# 99.net
KiCad netlist of a schematic drawn in EAGLE
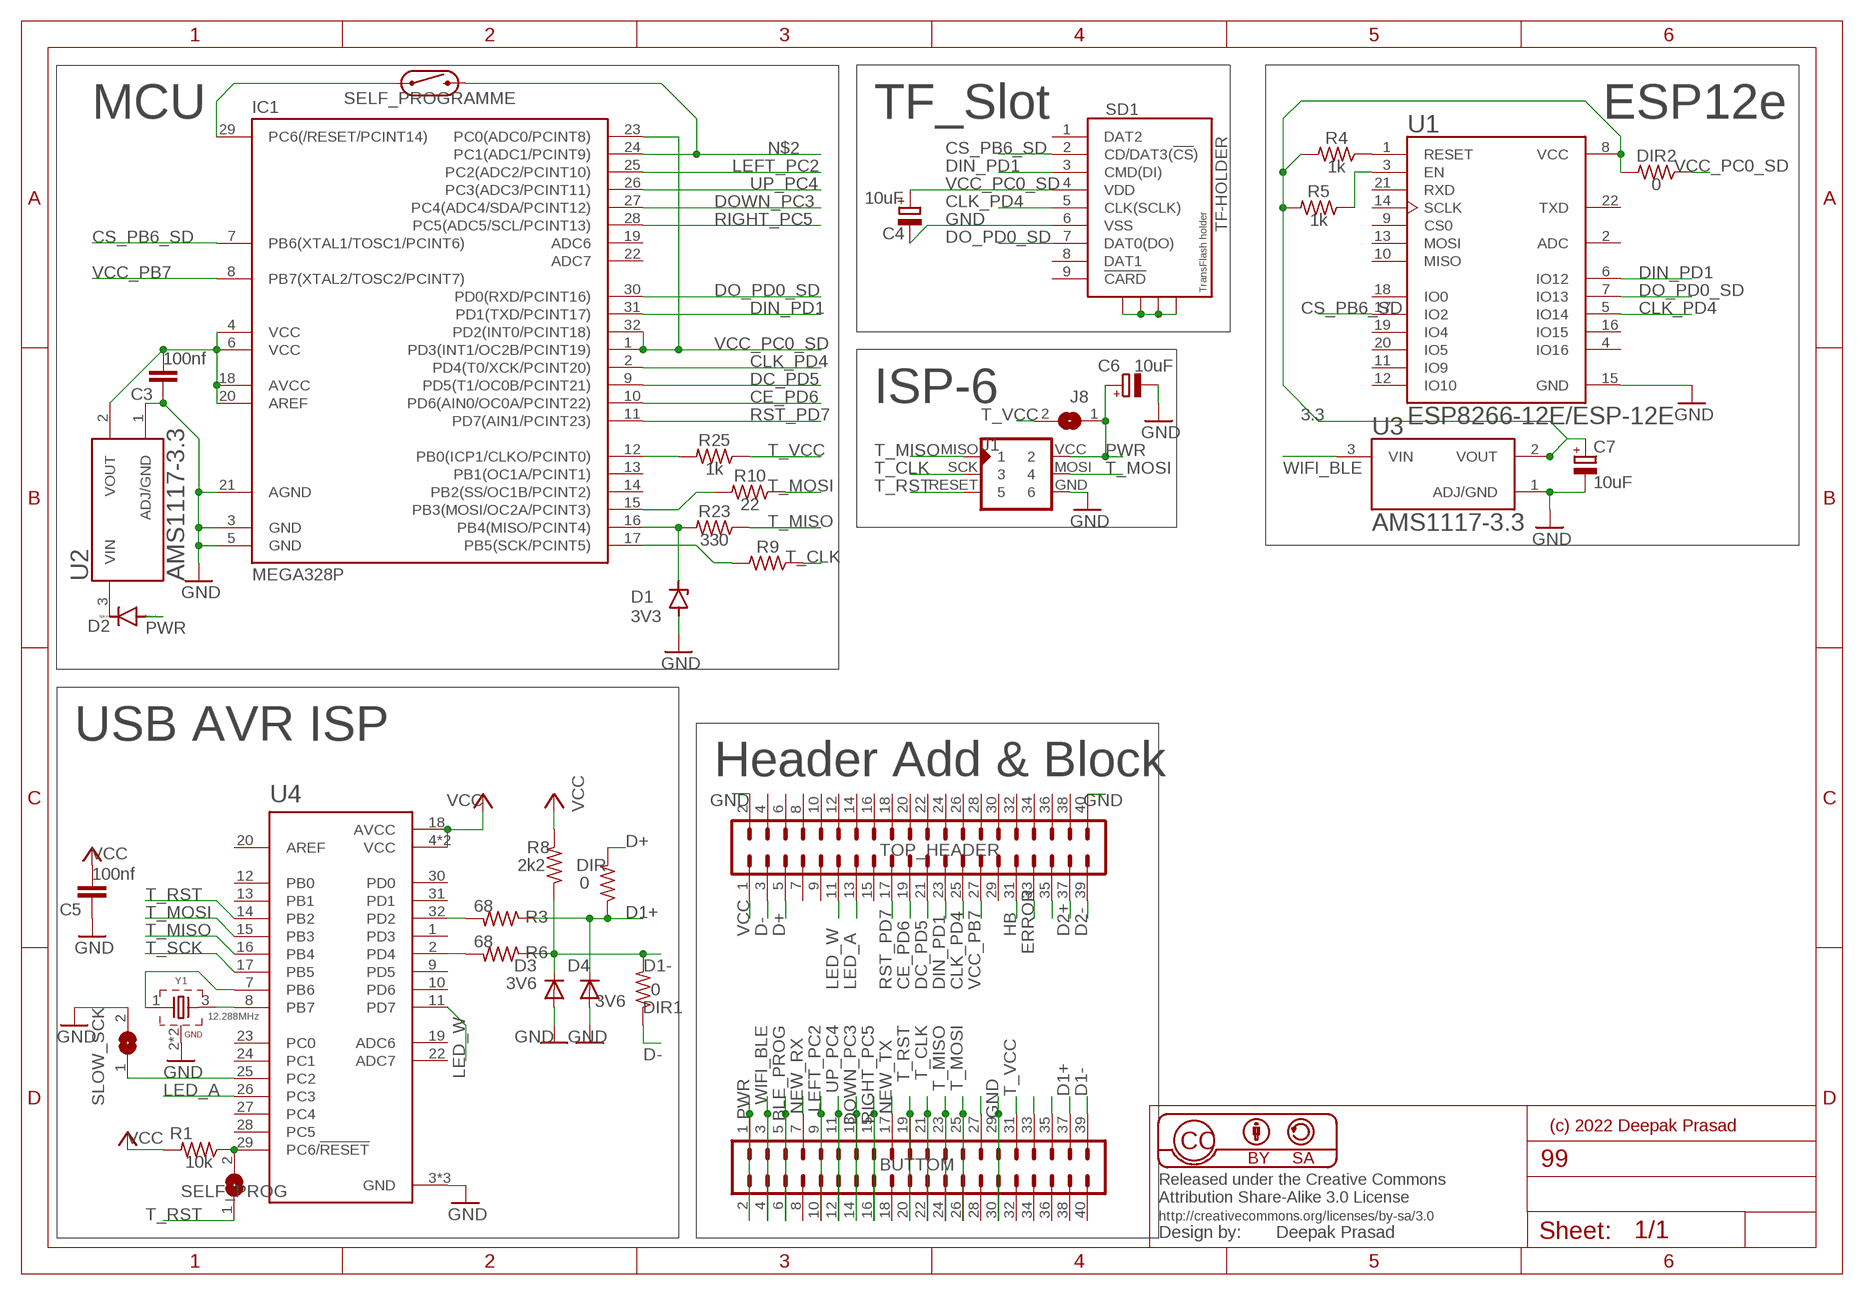
[diagram p0: schematic, sheet 1]

(export (version "E")
  (design (tool "Eeschema 10.0.6"))
  (components
    (comp (ref "BUTTOM")
      (value "MA20-2")
      (footprint "eagle-import:MA20-2")
      (libsource (lib "eagle-import") (part "MA20-2"))
    )
    (comp (ref "C3")
      (value "100nf")
      (footprint "eagle-import:C1206")
      (libsource (lib "eagle-import") (part "C-EUC1206"))
    )
    (comp (ref "C4")
      (value "10uF")
      (footprint "eagle-import:C_6032-28R")
      (libsource (lib "eagle-import") (part "CPOL-EUC/6032-28R"))
    )
    (comp (ref "C5")
      (value "100nf")
      (footprint "eagle-import:C1206")
      (libsource (lib "eagle-import") (part "C-EUC1206"))
    )
    (comp (ref "C6")
      (value "10uF")
      (footprint "eagle-import:C_6032-28R")
      (libsource (lib "eagle-import") (part "CPOL-EUC/6032-28R"))
    )
    (comp (ref "C7")
      (value "10uF")
      (footprint "eagle-import:C_6032-28R")
      (libsource (lib "eagle-import") (part "CPOL-EUC/6032-28R"))
    )
    (comp (ref "D1")
      (value "3V3")
      (footprint "eagle-import:SOD80C")
      (libsource (lib "eagle-import") (part "ZENER-DIODESOD80C"))
    )
    (comp (ref "D2")
      (value "DIODE-DO214AC")
      (footprint "eagle-import:DO214AC")
      (libsource (lib "eagle-import") (part "DIODE-DO214AC"))
    )
    (comp (ref "D3")
      (value "3V6")
      (footprint "eagle-import:SMA-DIODE")
      (libsource (lib "eagle-import") (part "DIODESMA"))
    )
    (comp (ref "D4")
      (value "3V6")
      (footprint "eagle-import:SMA-DIODE")
      (libsource (lib "eagle-import") (part "DIODESMA"))
    )
    (comp (ref "DIR")
      (value "0")
      (footprint "eagle-import:RESC3216X70")
      (libsource (lib "eagle-import") (part "R-USCHIP-1206(3216-METRIC)_"))
    )
    (comp (ref "DIR1")
      (value "0")
      (footprint "eagle-import:RESC3216X70")
      (libsource (lib "eagle-import") (part "R-USCHIP-1206(3216-METRIC)_"))
    )
    (comp (ref "DIR2")
      (value "0")
      (footprint "eagle-import:RESC3216X70")
      (libsource (lib "eagle-import") (part "R-USCHIP-1206(3216-METRIC)_"))
    )
    (comp (ref "IC1")
      (value "MEGA328P")
      (footprint "eagle-import:TQFP32-08")
      (libsource (lib "eagle-import") (part "MEGA48/88/168-AU"))
    )
    (comp (ref "J1")
      (value "AVR-ISP-6PINAVR-ISP-6PIN")
      (footprint "eagle-import:AVR-ISP-6PIN")
      (libsource (lib "eagle-import") (part "AVR-ISP-6PINAVR-ISP-6PIN"))
    )
    (comp (ref "J8")
      (value "SJW")
      (footprint "eagle-import:SJW")
      (libsource (lib "eagle-import") (part "SJW"))
    )
    (comp (ref "R1")
      (value "10k")
      (footprint "eagle-import:RESC3216X70")
      (libsource (lib "eagle-import") (part "R-USCHIP-1206(3216-METRIC)_"))
    )
    (comp (ref "R3")
      (value "68")
      (footprint "eagle-import:RESC3216X70")
      (libsource (lib "eagle-import") (part "R-USCHIP-1206(3216-METRIC)_"))
    )
    (comp (ref "R4")
      (value "1k")
      (footprint "eagle-import:RESC3216X70")
      (libsource (lib "eagle-import") (part "R-USCHIP-1206(3216-METRIC)_"))
    )
    (comp (ref "R5")
      (value "1k")
      (footprint "eagle-import:RESC3216X70")
      (libsource (lib "eagle-import") (part "R-USCHIP-1206(3216-METRIC)_"))
    )
    (comp (ref "R6")
      (value "68")
      (footprint "eagle-import:RESC3216X70")
      (libsource (lib "eagle-import") (part "R-USCHIP-1206(3216-METRIC)_"))
    )
    (comp (ref "R8")
      (value "2k2")
      (footprint "eagle-import:RESC3216X70")
      (libsource (lib "eagle-import") (part "R-USCHIP-1206(3216-METRIC)_"))
    )
    (comp (ref "R9")
      (value "22")
      (footprint "eagle-import:RESC3216X70")
      (libsource (lib "eagle-import") (part "R-USCHIP-1206(3216-METRIC)_"))
    )
    (comp (ref "R10")
      (value "22")
      (footprint "eagle-import:RESC3216X70")
      (libsource (lib "eagle-import") (part "R-USCHIP-1206(3216-METRIC)_"))
    )
    (comp (ref "R23")
      (value "330")
      (footprint "eagle-import:RESC3216X70")
      (libsource (lib "eagle-import") (part "R-USCHIP-1206(3216-METRIC)_"))
    )
    (comp (ref "R25")
      (value "1k")
      (footprint "eagle-import:RESC3216X70")
      (libsource (lib "eagle-import") (part "R-USCHIP-1206(3216-METRIC)_"))
    )
    (comp (ref "SD1")
      (value "TF-HOLDER")
      (footprint "eagle-import:TF-PULL")
      (libsource (lib "eagle-import") (part "TF-HOLDER"))
    )
    (comp (ref "SELF_PROG")
      (value "SJW")
      (footprint "eagle-import:SJW")
      (libsource (lib "eagle-import") (part "SJW"))
    )
    (comp (ref "SELF_PROGRAMME")
      (value "REED_SWITCH-PTH-GLASS")
      (footprint "eagle-import:REED_SWITCH_GLASS")
      (libsource (lib "eagle-import") (part "REED_SWITCH-PTH-GLASS"))
    )
    (comp (ref "SLOW_SCK")
      (value "SJW")
      (footprint "eagle-import:SJW")
      (libsource (lib "eagle-import") (part "SJW"))
    )
    (comp (ref "TOP_HEADER")
      (value "MA20-2")
      (footprint "eagle-import:MA20-2")
      (libsource (lib "eagle-import") (part "MA20-2"))
    )
    (comp (ref "U1")
      (value "ESP8266-12E/ESP-12E")
      (footprint "eagle-import:XCVR_ESP8266-12E_ESP-12E")
      (fields (field (name "MF") "AI-Thinker"))
      (libsource (lib "eagle-import") (part "ESP8266-12E/ESP-12E"))
    )
    (comp (ref "U2")
      (value "AMS1117-3.3")
      (footprint "eagle-import:SOT229P700X180-4N")
      (fields (field (name "MF") "Advanced Monolithic Systems"))
      (libsource (lib "eagle-import") (part "AMS1117-3.3"))
    )
    (comp (ref "U3")
      (value "AMS1117-3.3")
      (footprint "eagle-import:SOT229P700X180-4N")
      (fields (field (name "MF") "Advanced Monolithic Systems"))
      (libsource (lib "eagle-import") (part "AMS1117-3.3"))
    )
    (comp (ref "U4")
      (value "ATMEGA328P-AU")
      (footprint "eagle-import:QFP80P900X900X120-32N")
      (fields (field (name "MF") "Microchip Technology"))
      (libsource (lib "eagle-import") (part "ATMEGA328P-AU"))
    )
    (comp (ref "Y1")
      (value "12.288MHz")
      (footprint "eagle-import:WE-XTAL_CFPX-104")
      (fields (field (name "TOLERANCE") "±20ppm"))
      (libsource (lib "eagle-import") (part "WE-XTAL_CFPX-104_830059523"))
    )
  )
  (nets
    (net (code "1") (name "/3.3") (class "Default")
      (node (ref "C7") (pin "+") (pinfunction "+_+") (pintype "passive"))
      (node (ref "DIR2") (pin "2") (pinfunction "2_2") (pintype "passive"))
      (node (ref "R4") (pin "2") (pinfunction "2_2") (pintype "passive"))
      (node (ref "R5") (pin "2") (pinfunction "2_2") (pintype "passive"))
      (node (ref "U1") (pin "8") (pinfunction "VCC_8") (pintype "power_in"))
      (node (ref "U3") (pin "2") (pinfunction "VOUT_2") (pintype "output"))
    )
    (net (code "2") (name "/BLE_PROG") (class "Default")
      (node (ref "BUTTOM") (pin "5") (pinfunction "5_5") (pintype "passive"))
      (node (ref "BUTTOM") (pin "6") (pinfunction "6_6") (pintype "passive"))
    )
    (net (code "3") (name "/CE_PD6") (class "Default")
      (node (ref "IC1") (pin "10") (pinfunction "PD6(AIN0/OC0A/PCINT22)_10") (pintype "bidirectional"))
      (node (ref "TOP_HEADER") (pin "19") (pinfunction "19_19") (pintype "passive"))
    )
    (net (code "4") (name "/CLK_PD4") (class "Default")
      (node (ref "IC1") (pin "2") (pinfunction "PD4(T0/XCK/PCINT20)_2") (pintype "bidirectional"))
      (node (ref "SD1") (pin "5") (pinfunction "CLK(SCLK)_5") (pintype "input"))
      (node (ref "TOP_HEADER") (pin "25") (pinfunction "25_25") (pintype "passive"))
      (node (ref "U1") (pin "5") (pinfunction "IO14_5") (pintype "bidirectional"))
    )
    (net (code "5") (name "/CS_PB6_SD") (class "Default")
      (node (ref "IC1") (pin "7") (pinfunction "PB6(XTAL1/TOSC1/PCINT6)_7") (pintype "bidirectional"))
      (node (ref "SD1") (pin "2") (pinfunction "CD/DAT3(~{CS})_2") (pintype "bidirectional"))
      (node (ref "U1") (pin "17") (pinfunction "IO2_17") (pintype "bidirectional"))
    )
    (net (code "6") (name "/D+") (class "Default")
      (node (ref "DIR") (pin "2") (pinfunction "2_2") (pintype "passive"))
      (node (ref "TOP_HEADER") (pin "5") (pinfunction "5_5") (pintype "passive"))
    )
    (net (code "7") (name "/D-") (class "Default")
      (node (ref "DIR1") (pin "1") (pinfunction "1_1") (pintype "passive"))
      (node (ref "TOP_HEADER") (pin "3") (pinfunction "3_3") (pintype "passive"))
    )
    (net (code "8") (name "/D1+") (class "Default")
      (node (ref "BUTTOM") (pin "37") (pinfunction "37_37") (pintype "passive"))
      (node (ref "D4") (pin "C") (pinfunction "C_C") (pintype "passive"))
      (node (ref "DIR") (pin "1") (pinfunction "1_1") (pintype "passive"))
      (node (ref "R3") (pin "1") (pinfunction "1_1") (pintype "passive"))
    )
    (net (code "9") (name "/D1-") (class "Default")
      (node (ref "BUTTOM") (pin "39") (pinfunction "39_39") (pintype "passive"))
      (node (ref "D3") (pin "C") (pinfunction "C_C") (pintype "passive"))
      (node (ref "DIR1") (pin "2") (pinfunction "2_2") (pintype "passive"))
      (node (ref "R6") (pin "1") (pinfunction "1_1") (pintype "passive"))
      (node (ref "R8") (pin "1") (pinfunction "1_1") (pintype "passive"))
    )
    (net (code "10") (name "/D2+") (class "Default")
      (node (ref "TOP_HEADER") (pin "37") (pinfunction "37_37") (pintype "passive"))
    )
    (net (code "11") (name "/D2-") (class "Default")
      (node (ref "TOP_HEADER") (pin "39") (pinfunction "39_39") (pintype "passive"))
    )
    (net (code "12") (name "/DC_PD5") (class "Default")
      (node (ref "IC1") (pin "9") (pinfunction "PD5(T1/OC0B/PCINT21)_9") (pintype "bidirectional"))
      (node (ref "TOP_HEADER") (pin "21") (pinfunction "21_21") (pintype "passive"))
    )
    (net (code "13") (name "/DIN_PD1") (class "Default")
      (node (ref "IC1") (pin "31") (pinfunction "PD1(TXD/PCINT17)_31") (pintype "bidirectional"))
      (node (ref "SD1") (pin "3") (pinfunction "CMD(DI)_3") (pintype "bidirectional"))
      (node (ref "TOP_HEADER") (pin "23") (pinfunction "23_23") (pintype "passive"))
      (node (ref "U1") (pin "6") (pinfunction "IO12_6") (pintype "bidirectional"))
    )
    (net (code "14") (name "/DOWN_PC3") (class "Default")
      (node (ref "BUTTOM") (pin "13") (pinfunction "13_13") (pintype "passive"))
      (node (ref "BUTTOM") (pin "14") (pinfunction "14_14") (pintype "passive"))
      (node (ref "IC1") (pin "27") (pinfunction "PC4(ADC4/SDA/PCINT12)_27") (pintype "bidirectional"))
    )
    (net (code "15") (name "/DO_PD0_SD") (class "Default")
      (node (ref "IC1") (pin "30") (pinfunction "PD0(RXD/PCINT16)_30") (pintype "bidirectional"))
      (node (ref "SD1") (pin "7") (pinfunction "DAT0(DO)_7") (pintype "bidirectional"))
      (node (ref "U1") (pin "7") (pinfunction "IO13_7") (pintype "bidirectional"))
    )
    (net (code "16") (name "/ERROR") (class "Default")
      (node (ref "TOP_HEADER") (pin "33") (pinfunction "33_33") (pintype "passive"))
    )
    (net (code "17") (name "/HB") (class "Default")
      (node (ref "TOP_HEADER") (pin "31") (pinfunction "31_31") (pintype "passive"))
    )
    (net (code "18") (name "/LED_A") (class "Default")
      (node (ref "TOP_HEADER") (pin "13") (pinfunction "13_13") (pintype "passive"))
      (node (ref "U4") (pin "26") (pinfunction "PC3_26") (pintype "bidirectional"))
    )
    (net (code "19") (name "/LED_W") (class "Default")
      (node (ref "TOP_HEADER") (pin "11") (pinfunction "11_11") (pintype "passive"))
      (node (ref "U4") (pin "11") (pinfunction "PD7_11") (pintype "bidirectional"))
    )
    (net (code "20") (name "/LEFT_PC2") (class "Default")
      (node (ref "BUTTOM") (pin "10") (pinfunction "10_10") (pintype "passive"))
      (node (ref "BUTTOM") (pin "9") (pinfunction "9_9") (pintype "passive"))
      (node (ref "IC1") (pin "25") (pinfunction "PC2(ADC2/PCINT10)_25") (pintype "bidirectional"))
    )
    (net (code "21") (name "/N$2") (class "Default")
      (node (ref "IC1") (pin "24") (pinfunction "PC1(ADC1/PCINT9)_24") (pintype "bidirectional"))
      (node (ref "SELF_PROGRAMME") (pin "P$2") (pinfunction "2_P$2") (pintype "passive"))
    )
    (net (code "22") (name "/NEW_RX") (class "Default")
      (node (ref "BUTTOM") (pin "7") (pinfunction "7_7") (pintype "passive"))
    )
    (net (code "23") (name "/NEW_TX") (class "Default")
      (node (ref "BUTTOM") (pin "17") (pinfunction "17_17") (pintype "passive"))
    )
    (net (code "24") (name "/PWR") (class "Default")
      (node (ref "BUTTOM") (pin "1") (pinfunction "1_1") (pintype "passive"))
      (node (ref "BUTTOM") (pin "2") (pinfunction "2_2") (pintype "passive"))
      (node (ref "C6") (pin "+") (pinfunction "+_+") (pintype "passive"))
      (node (ref "D2") (pin "A") (pinfunction "A_A") (pintype "passive"))
      (node (ref "J1") (pin "VCC") (pinfunction "2_VCC") (pintype "passive"))
      (node (ref "J8") (pin "1") (pinfunction "1_1") (pintype "passive"))
    )
    (net (code "25") (name "/RIGHT_PC5") (class "Default")
      (node (ref "BUTTOM") (pin "15") (pinfunction "15_15") (pintype "passive"))
      (node (ref "BUTTOM") (pin "16") (pinfunction "16_16") (pintype "passive"))
      (node (ref "IC1") (pin "28") (pinfunction "PC5(ADC5/SCL/PCINT13)_28") (pintype "bidirectional"))
    )
    (net (code "26") (name "/RST_PD7") (class "Default")
      (node (ref "IC1") (pin "11") (pinfunction "PD7(AIN1/PCINT23)_11") (pintype "bidirectional"))
      (node (ref "TOP_HEADER") (pin "17") (pinfunction "17_17") (pintype "passive"))
    )
    (net (code "27") (name "/T_CLK") (class "Default")
      (node (ref "BUTTOM") (pin "21") (pinfunction "21_21") (pintype "passive"))
      (node (ref "BUTTOM") (pin "22") (pinfunction "22_22") (pintype "passive"))
      (node (ref "J1") (pin "SCK") (pinfunction "3_SCK") (pintype "passive"))
      (node (ref "R9") (pin "1") (pinfunction "1_1") (pintype "passive"))
    )
    (net (code "28") (name "/T_MISO") (class "Default")
      (node (ref "BUTTOM") (pin "23") (pinfunction "23_23") (pintype "passive"))
      (node (ref "BUTTOM") (pin "24") (pinfunction "24_24") (pintype "passive"))
      (node (ref "J1") (pin "MISO") (pinfunction "1_MISO") (pintype "passive"))
      (node (ref "R23") (pin "1") (pinfunction "1_1") (pintype "passive"))
      (node (ref "U4") (pin "16") (pinfunction "PB4_16") (pintype "bidirectional"))
    )
    (net (code "29") (name "/T_MOSI") (class "Default")
      (node (ref "BUTTOM") (pin "25") (pinfunction "25_25") (pintype "passive"))
      (node (ref "BUTTOM") (pin "26") (pinfunction "26_26") (pintype "passive"))
      (node (ref "J1") (pin "MOSI") (pinfunction "4_MOSI") (pintype "passive"))
      (node (ref "R10") (pin "1") (pinfunction "1_1") (pintype "passive"))
      (node (ref "U4") (pin "15") (pinfunction "PB3_15") (pintype "bidirectional"))
    )
    (net (code "30") (name "/T_RST") (class "Default")
      (node (ref "BUTTOM") (pin "19") (pinfunction "19_19") (pintype "passive"))
      (node (ref "BUTTOM") (pin "20") (pinfunction "20_20") (pintype "passive"))
      (node (ref "J1") (pin "RESET") (pinfunction "5_RESET") (pintype "passive"))
      (node (ref "SELF_PROG") (pin "1") (pinfunction "1_1") (pintype "passive"))
      (node (ref "U4") (pin "14") (pinfunction "PB2_14") (pintype "bidirectional"))
    )
    (net (code "31") (name "/T_SCK") (class "Default")
      (node (ref "U4") (pin "17") (pinfunction "PB5_17") (pintype "bidirectional"))
    )
    (net (code "32") (name "/T_VCC") (class "Default")
      (node (ref "BUTTOM") (pin "31") (pinfunction "31_31") (pintype "passive"))
      (node (ref "J8") (pin "2") (pinfunction "2_2") (pintype "passive"))
      (node (ref "R25") (pin "1") (pinfunction "1_1") (pintype "passive"))
    )
    (net (code "33") (name "/UP_PC4") (class "Default")
      (node (ref "BUTTOM") (pin "11") (pinfunction "11_11") (pintype "passive"))
      (node (ref "BUTTOM") (pin "12") (pinfunction "12_12") (pintype "passive"))
      (node (ref "IC1") (pin "26") (pinfunction "PC3(ADC3/PCINT11)_26") (pintype "bidirectional"))
    )
    (net (code "34") (name "/VCC_PB7") (class "Default")
      (node (ref "IC1") (pin "8") (pinfunction "PB7(XTAL2/TOSC2/PCINT7)_8") (pintype "bidirectional"))
      (node (ref "TOP_HEADER") (pin "27") (pinfunction "27_27") (pintype "passive"))
    )
    (net (code "35") (name "/VCC_PC0_SD") (class "Default")
      (node (ref "C4") (pin "+") (pinfunction "+_+") (pintype "passive"))
      (node (ref "DIR2") (pin "1") (pinfunction "1_1") (pintype "passive"))
      (node (ref "IC1") (pin "1") (pinfunction "PD3(INT1/OC2B/PCINT19)_1") (pintype "bidirectional"))
      (node (ref "IC1") (pin "23") (pinfunction "PC0(ADC0/PCINT8)_23") (pintype "bidirectional"))
      (node (ref "IC1") (pin "32") (pinfunction "PD2(INT0/PCINT18)_32") (pintype "bidirectional"))
      (node (ref "SD1") (pin "4") (pinfunction "VDD_4") (pintype "power_in"))
    )
    (net (code "36") (name "/WIFI_BLE") (class "Default")
      (node (ref "BUTTOM") (pin "3") (pinfunction "3_3") (pintype "passive"))
      (node (ref "BUTTOM") (pin "4") (pinfunction "4_4") (pintype "passive"))
      (node (ref "U3") (pin "3") (pinfunction "VIN_3") (pintype "input"))
    )
    (net (code "37") (name "GND") (class "Default")
      (node (ref "BUTTOM") (pin "29") (pinfunction "29_29") (pintype "passive"))
      (node (ref "BUTTOM") (pin "30") (pinfunction "30_30") (pintype "passive"))
      (node (ref "C3") (pin "1") (pinfunction "1_1") (pintype "passive"))
      (node (ref "C4") (pin "-") (pinfunction "-_-") (pintype "passive"))
      (node (ref "C5") (pin "1") (pinfunction "1_1") (pintype "passive"))
      (node (ref "C6") (pin "-") (pinfunction "-_-") (pintype "passive"))
      (node (ref "C7") (pin "-") (pinfunction "-_-") (pintype "passive"))
      (node (ref "D1") (pin "A") (pinfunction "A_A") (pintype "passive"))
      (node (ref "D3") (pin "A") (pinfunction "A_A") (pintype "passive"))
      (node (ref "D4") (pin "A") (pinfunction "A_A") (pintype "passive"))
      (node (ref "IC1") (pin "21") (pinfunction "AGND_21") (pintype "power_in"))
      (node (ref "IC1") (pin "3") (pinfunction "GND_3") (pintype "power_in"))
      (node (ref "IC1") (pin "5") (pinfunction "GND_5") (pintype "power_in"))
      (node (ref "J1") (pin "GND") (pinfunction "6_GND") (pintype "passive"))
      (node (ref "SD1") (pin "6") (pinfunction "VSS_6") (pintype "power_in"))
      (node (ref "SLOW_SCK") (pin "2") (pinfunction "2_2") (pintype "passive"))
      (node (ref "TOP_HEADER") (pin "2") (pinfunction "2_2") (pintype "passive"))
      (node (ref "TOP_HEADER") (pin "40") (pinfunction "40_40") (pintype "passive"))
      (node (ref "U1") (pin "15") (pinfunction "GND_15") (pintype "power_in"))
      (node (ref "U2") (pin "1") (pinfunction "ADJ/GND_1") (pintype "power_in"))
      (node (ref "U3") (pin "1") (pinfunction "ADJ/GND_1") (pintype "power_in"))
      (node (ref "U4") (pin "21") (pinfunction "GND_21") (pintype "power_in"))
      (node (ref "U4") (pin "3") (pinfunction "GND_3") (pintype "power_in"))
      (node (ref "U4") (pin "5") (pinfunction "GND_5") (pintype "power_in"))
      (node (ref "Y1") (pin "2") (pinfunction "GND_2") (pintype "passive"))
      (node (ref "Y1") (pin "4") (pinfunction "GND_4") (pintype "passive"))
    )
    (net (code "38") (name "Net-(IC1-AREF)") (class "Default")
      (node (ref "C3") (pin "2") (pinfunction "2_2") (pintype "passive"))
      (node (ref "IC1") (pin "18") (pinfunction "AVCC_18") (pintype "passive"))
      (node (ref "IC1") (pin "20") (pinfunction "AREF_20") (pintype "passive"))
      (node (ref "IC1") (pin "4") (pinfunction "VCC_4") (pintype "power_in"))
      (node (ref "IC1") (pin "6") (pinfunction "VCC_6") (pintype "power_in"))
      (node (ref "U2") (pin "2") (pinfunction "VOUT_2") (pintype "output"))
    )
    (net (code "39") (name "Net-(IC1-PB0(ICP1{slash}CLKO{slash}PCINT0))") (class "Default")
      (node (ref "IC1") (pin "12") (pinfunction "PB0(ICP1/CLKO/PCINT0)_12") (pintype "bidirectional"))
      (node (ref "R25") (pin "2") (pinfunction "2_2") (pintype "passive"))
    )
    (net (code "40") (name "Net-(IC1-PB3(MOSI{slash}OC2A{slash}PCINT3))") (class "Default")
      (node (ref "IC1") (pin "15") (pinfunction "PB3(MOSI/OC2A/PCINT3)_15") (pintype "bidirectional"))
      (node (ref "R10") (pin "2") (pinfunction "2_2") (pintype "passive"))
    )
    (net (code "41") (name "Net-(IC1-PB4(MISO{slash}PCINT4))") (class "Default")
      (node (ref "D1") (pin "C") (pinfunction "C_C") (pintype "passive"))
      (node (ref "IC1") (pin "16") (pinfunction "PB4(MISO/PCINT4)_16") (pintype "bidirectional"))
      (node (ref "R23") (pin "2") (pinfunction "2_2") (pintype "passive"))
    )
    (net (code "42") (name "Net-(IC1-PB5(SCK{slash}PCINT5))") (class "Default")
      (node (ref "IC1") (pin "17") (pinfunction "PB5(SCK/PCINT5)_17") (pintype "bidirectional"))
      (node (ref "R9") (pin "2") (pinfunction "2_2") (pintype "passive"))
    )
    (net (code "43") (name "Net-(IC1-PC6({slash}RESET{slash}PCINT14))") (class "Default")
      (node (ref "IC1") (pin "29") (pinfunction "PC6(/RESET/PCINT14)_29") (pintype "bidirectional"))
      (node (ref "SELF_PROGRAMME") (pin "P$1") (pinfunction "1_P$1") (pintype "passive"))
    )
    (net (code "44") (name "Net-(SD1-PadS1)") (class "Default")
      (node (ref "SD1") (pin "S1") (pinfunction "S1_S1") (pintype "passive"))
      (node (ref "SD1") (pin "S2") (pinfunction "S2_S2") (pintype "passive"))
      (node (ref "SD1") (pin "S3") (pinfunction "S3_S3") (pintype "passive"))
      (node (ref "SD1") (pin "S4") (pinfunction "S4_S4") (pintype "passive"))
    )
    (net (code "45") (name "Net-(U1-EN)") (class "Default")
      (node (ref "R5") (pin "1") (pinfunction "1_1") (pintype "passive"))
      (node (ref "U1") (pin "3") (pinfunction "EN_3") (pintype "input"))
    )
    (net (code "46") (name "Net-(U1-RESET)") (class "Default")
      (node (ref "R4") (pin "1") (pinfunction "1_1") (pintype "passive"))
      (node (ref "U1") (pin "1") (pinfunction "RESET_1") (pintype "input"))
    )
    (net (code "47") (name "Net-(U2-VIN)") (class "Default")
      (node (ref "D2") (pin "C") (pinfunction "C_C") (pintype "passive"))
      (node (ref "U2") (pin "3") (pinfunction "VIN_3") (pintype "input"))
    )
    (net (code "48") (name "Net-(U4-PB6)") (class "Default")
      (node (ref "U4") (pin "7") (pinfunction "PB6_7") (pintype "bidirectional"))
      (node (ref "Y1") (pin "1") (pinfunction "1_1") (pintype "passive"))
    )
    (net (code "49") (name "Net-(U4-PB7)") (class "Default")
      (node (ref "U4") (pin "8") (pinfunction "PB7_8") (pintype "bidirectional"))
      (node (ref "Y1") (pin "3") (pinfunction "2_3") (pintype "passive"))
    )
    (net (code "50") (name "Net-(U4-PC2)") (class "Default")
      (node (ref "SLOW_SCK") (pin "1") (pinfunction "1_1") (pintype "passive"))
      (node (ref "U4") (pin "25") (pinfunction "PC2_25") (pintype "bidirectional"))
    )
    (net (code "51") (name "Net-(U4-PC6{slash}~{RESET})") (class "Default")
      (node (ref "R1") (pin "1") (pinfunction "1_1") (pintype "passive"))
      (node (ref "SELF_PROG") (pin "2") (pinfunction "2_2") (pintype "passive"))
      (node (ref "U4") (pin "29") (pinfunction "PC6/~{RESET}_29") (pintype "bidirectional"))
    )
    (net (code "52") (name "Net-(U4-PD2)") (class "Default")
      (node (ref "R3") (pin "2") (pinfunction "2_2") (pintype "passive"))
      (node (ref "U4") (pin "32") (pinfunction "PD2_32") (pintype "bidirectional"))
    )
    (net (code "53") (name "Net-(U4-PD4)") (class "Default")
      (node (ref "R6") (pin "2") (pinfunction "2_2") (pintype "passive"))
      (node (ref "U4") (pin "2") (pinfunction "PD4_2") (pintype "bidirectional"))
    )
    (net (code "54") (name "VCC") (class "Default")
      (node (ref "C5") (pin "2") (pinfunction "2_2") (pintype "passive"))
      (node (ref "R1") (pin "2") (pinfunction "2_2") (pintype "passive"))
      (node (ref "R8") (pin "2") (pinfunction "2_2") (pintype "passive"))
      (node (ref "TOP_HEADER") (pin "1") (pinfunction "1_1") (pintype "passive"))
      (node (ref "U4") (pin "18") (pinfunction "AVCC_18") (pintype "power_in"))
      (node (ref "U4") (pin "4") (pinfunction "VCC_4") (pintype "power_in"))
      (node (ref "U4") (pin "6") (pinfunction "VCC_6") (pintype "power_in"))
    )
    (net (code "55") (name "unconnected-(BUTTOM-Pad8)") (class "Default")
      (node (ref "BUTTOM") (pin "8") (pinfunction "8_8") (pintype "passive"))
    )
    (net (code "56") (name "unconnected-(BUTTOM-Pad18)") (class "Default")
      (node (ref "BUTTOM") (pin "18") (pinfunction "18_18") (pintype "passive"))
    )
    (net (code "57") (name "unconnected-(BUTTOM-Pad27)") (class "Default")
      (node (ref "BUTTOM") (pin "27") (pinfunction "27_27") (pintype "passive"))
    )
    (net (code "58") (name "unconnected-(BUTTOM-Pad28)") (class "Default")
      (node (ref "BUTTOM") (pin "28") (pinfunction "28_28") (pintype "passive"))
    )
    (net (code "59") (name "unconnected-(BUTTOM-Pad32)") (class "Default")
      (node (ref "BUTTOM") (pin "32") (pinfunction "32_32") (pintype "passive"))
    )
    (net (code "60") (name "unconnected-(BUTTOM-Pad33)") (class "Default")
      (node (ref "BUTTOM") (pin "33") (pinfunction "33_33") (pintype "passive"))
    )
    (net (code "61") (name "unconnected-(BUTTOM-Pad34)") (class "Default")
      (node (ref "BUTTOM") (pin "34") (pinfunction "34_34") (pintype "passive"))
    )
    (net (code "62") (name "unconnected-(BUTTOM-Pad35)") (class "Default")
      (node (ref "BUTTOM") (pin "35") (pinfunction "35_35") (pintype "passive"))
    )
    (net (code "63") (name "unconnected-(BUTTOM-Pad36)") (class "Default")
      (node (ref "BUTTOM") (pin "36") (pinfunction "36_36") (pintype "passive"))
    )
    (net (code "64") (name "unconnected-(BUTTOM-Pad38)") (class "Default")
      (node (ref "BUTTOM") (pin "38") (pinfunction "38_38") (pintype "passive"))
    )
    (net (code "65") (name "unconnected-(BUTTOM-Pad40)") (class "Default")
      (node (ref "BUTTOM") (pin "40") (pinfunction "40_40") (pintype "passive"))
    )
    (net (code "66") (name "unconnected-(IC1-ADC6-Pad19)") (class "Default")
      (node (ref "IC1") (pin "19") (pinfunction "ADC6_19") (pintype "passive"))
    )
    (net (code "67") (name "unconnected-(IC1-ADC7-Pad22)") (class "Default")
      (node (ref "IC1") (pin "22") (pinfunction "ADC7_22") (pintype "passive"))
    )
    (net (code "68") (name "unconnected-(IC1-PB1(OC1A{slash}PCINT1)-Pad13)") (class "Default")
      (node (ref "IC1") (pin "13") (pinfunction "PB1(OC1A/PCINT1)_13") (pintype "bidirectional"))
    )
    (net (code "69") (name "unconnected-(IC1-PB2(SS{slash}OC1B{slash}PCINT2)-Pad14)") (class "Default")
      (node (ref "IC1") (pin "14") (pinfunction "PB2(SS/OC1B/PCINT2)_14") (pintype "bidirectional"))
    )
    (net (code "70") (name "unconnected-(SD1-DAT1-Pad8)") (class "Default")
      (node (ref "SD1") (pin "8") (pinfunction "DAT1_8") (pintype "bidirectional"))
    )
    (net (code "71") (name "unconnected-(SD1-DAT2-Pad1)") (class "Default")
      (node (ref "SD1") (pin "1") (pinfunction "DAT2_1") (pintype "bidirectional"))
    )
    (net (code "72") (name "unconnected-(SD1-~{CARD}-Pad9)") (class "Default")
      (node (ref "SD1") (pin "9") (pinfunction "~{CARD}_9") (pintype "passive"))
    )
    (net (code "73") (name "unconnected-(TOP_HEADER-Pad4)") (class "Default")
      (node (ref "TOP_HEADER") (pin "4") (pinfunction "4_4") (pintype "passive"))
    )
    (net (code "74") (name "unconnected-(TOP_HEADER-Pad6)") (class "Default")
      (node (ref "TOP_HEADER") (pin "6") (pinfunction "6_6") (pintype "passive"))
    )
    (net (code "75") (name "unconnected-(TOP_HEADER-Pad7)") (class "Default")
      (node (ref "TOP_HEADER") (pin "7") (pinfunction "7_7") (pintype "passive"))
    )
    (net (code "76") (name "unconnected-(TOP_HEADER-Pad8)") (class "Default")
      (node (ref "TOP_HEADER") (pin "8") (pinfunction "8_8") (pintype "passive"))
    )
    (net (code "77") (name "unconnected-(TOP_HEADER-Pad9)") (class "Default")
      (node (ref "TOP_HEADER") (pin "9") (pinfunction "9_9") (pintype "passive"))
    )
    (net (code "78") (name "unconnected-(TOP_HEADER-Pad10)") (class "Default")
      (node (ref "TOP_HEADER") (pin "10") (pinfunction "10_10") (pintype "passive"))
    )
    (net (code "79") (name "unconnected-(TOP_HEADER-Pad12)") (class "Default")
      (node (ref "TOP_HEADER") (pin "12") (pinfunction "12_12") (pintype "passive"))
    )
    (net (code "80") (name "unconnected-(TOP_HEADER-Pad14)") (class "Default")
      (node (ref "TOP_HEADER") (pin "14") (pinfunction "14_14") (pintype "passive"))
    )
    (net (code "81") (name "unconnected-(TOP_HEADER-Pad15)") (class "Default")
      (node (ref "TOP_HEADER") (pin "15") (pinfunction "15_15") (pintype "passive"))
    )
    (net (code "82") (name "unconnected-(TOP_HEADER-Pad16)") (class "Default")
      (node (ref "TOP_HEADER") (pin "16") (pinfunction "16_16") (pintype "passive"))
    )
    (net (code "83") (name "unconnected-(TOP_HEADER-Pad18)") (class "Default")
      (node (ref "TOP_HEADER") (pin "18") (pinfunction "18_18") (pintype "passive"))
    )
    (net (code "84") (name "unconnected-(TOP_HEADER-Pad20)") (class "Default")
      (node (ref "TOP_HEADER") (pin "20") (pinfunction "20_20") (pintype "passive"))
    )
    (net (code "85") (name "unconnected-(TOP_HEADER-Pad22)") (class "Default")
      (node (ref "TOP_HEADER") (pin "22") (pinfunction "22_22") (pintype "passive"))
    )
    (net (code "86") (name "unconnected-(TOP_HEADER-Pad24)") (class "Default")
      (node (ref "TOP_HEADER") (pin "24") (pinfunction "24_24") (pintype "passive"))
    )
    (net (code "87") (name "unconnected-(TOP_HEADER-Pad26)") (class "Default")
      (node (ref "TOP_HEADER") (pin "26") (pinfunction "26_26") (pintype "passive"))
    )
    (net (code "88") (name "unconnected-(TOP_HEADER-Pad28)") (class "Default")
      (node (ref "TOP_HEADER") (pin "28") (pinfunction "28_28") (pintype "passive"))
    )
    (net (code "89") (name "unconnected-(TOP_HEADER-Pad29)") (class "Default")
      (node (ref "TOP_HEADER") (pin "29") (pinfunction "29_29") (pintype "passive"))
    )
    (net (code "90") (name "unconnected-(TOP_HEADER-Pad30)") (class "Default")
      (node (ref "TOP_HEADER") (pin "30") (pinfunction "30_30") (pintype "passive"))
    )
    (net (code "91") (name "unconnected-(TOP_HEADER-Pad32)") (class "Default")
      (node (ref "TOP_HEADER") (pin "32") (pinfunction "32_32") (pintype "passive"))
    )
    (net (code "92") (name "unconnected-(TOP_HEADER-Pad34)") (class "Default")
      (node (ref "TOP_HEADER") (pin "34") (pinfunction "34_34") (pintype "passive"))
    )
    (net (code "93") (name "unconnected-(TOP_HEADER-Pad35)") (class "Default")
      (node (ref "TOP_HEADER") (pin "35") (pinfunction "35_35") (pintype "passive"))
    )
    (net (code "94") (name "unconnected-(TOP_HEADER-Pad36)") (class "Default")
      (node (ref "TOP_HEADER") (pin "36") (pinfunction "36_36") (pintype "passive"))
    )
    (net (code "95") (name "unconnected-(TOP_HEADER-Pad38)") (class "Default")
      (node (ref "TOP_HEADER") (pin "38") (pinfunction "38_38") (pintype "passive"))
    )
    (net (code "96") (name "unconnected-(U1-ADC-Pad2)") (class "Default")
      (node (ref "U1") (pin "2") (pinfunction "ADC_2") (pintype "passive"))
    )
    (net (code "97") (name "unconnected-(U1-CS0-Pad9)") (class "Default")
      (node (ref "U1") (pin "9") (pinfunction "CS0_9") (pintype "input"))
    )
    (net (code "98") (name "unconnected-(U1-IO0-Pad18)") (class "Default")
      (node (ref "U1") (pin "18") (pinfunction "IO0_18") (pintype "bidirectional"))
    )
    (net (code "99") (name "unconnected-(U1-IO4-Pad19)") (class "Default")
      (node (ref "U1") (pin "19") (pinfunction "IO4_19") (pintype "bidirectional"))
    )
    (net (code "100") (name "unconnected-(U1-IO5-Pad20)") (class "Default")
      (node (ref "U1") (pin "20") (pinfunction "IO5_20") (pintype "bidirectional"))
    )
    (net (code "101") (name "unconnected-(U1-IO9-Pad11)") (class "Default")
      (node (ref "U1") (pin "11") (pinfunction "IO9_11") (pintype "bidirectional"))
    )
    (net (code "102") (name "unconnected-(U1-IO10-Pad12)") (class "Default")
      (node (ref "U1") (pin "12") (pinfunction "IO10_12") (pintype "bidirectional"))
    )
    (net (code "103") (name "unconnected-(U1-IO15-Pad16)") (class "Default")
      (node (ref "U1") (pin "16") (pinfunction "IO15_16") (pintype "bidirectional"))
    )
    (net (code "104") (name "unconnected-(U1-IO16-Pad4)") (class "Default")
      (node (ref "U1") (pin "4") (pinfunction "IO16_4") (pintype "bidirectional"))
    )
    (net (code "105") (name "unconnected-(U1-MISO-Pad10)") (class "Default")
      (node (ref "U1") (pin "10") (pinfunction "MISO_10") (pintype "bidirectional"))
    )
    (net (code "106") (name "unconnected-(U1-MOSI-Pad13)") (class "Default")
      (node (ref "U1") (pin "13") (pinfunction "MOSI_13") (pintype "bidirectional"))
    )
    (net (code "107") (name "unconnected-(U1-RXD-Pad21)") (class "Default")
      (node (ref "U1") (pin "21") (pinfunction "RXD_21") (pintype "input"))
    )
    (net (code "108") (name "unconnected-(U1-SCLK-Pad14)") (class "Default")
      (node (ref "U1") (pin "14") (pinfunction "SCLK_14") (pintype "input"))
    )
    (net (code "109") (name "unconnected-(U1-TXD-Pad22)") (class "Default")
      (node (ref "U1") (pin "22") (pinfunction "TXD_22") (pintype "output"))
    )
    (net (code "110") (name "unconnected-(U4-ADC6-Pad19)") (class "Default")
      (node (ref "U4") (pin "19") (pinfunction "ADC6_19") (pintype "bidirectional"))
    )
    (net (code "111") (name "unconnected-(U4-ADC7-Pad22)") (class "Default")
      (node (ref "U4") (pin "22") (pinfunction "ADC7_22") (pintype "bidirectional"))
    )
    (net (code "112") (name "unconnected-(U4-AREF-Pad20)") (class "Default")
      (node (ref "U4") (pin "20") (pinfunction "AREF_20") (pintype "input"))
    )
    (net (code "113") (name "unconnected-(U4-PB0-Pad12)") (class "Default")
      (node (ref "U4") (pin "12") (pinfunction "PB0_12") (pintype "bidirectional"))
    )
    (net (code "114") (name "unconnected-(U4-PB1-Pad13)") (class "Default")
      (node (ref "U4") (pin "13") (pinfunction "PB1_13") (pintype "bidirectional"))
    )
    (net (code "115") (name "unconnected-(U4-PC0-Pad23)") (class "Default")
      (node (ref "U4") (pin "23") (pinfunction "PC0_23") (pintype "bidirectional"))
    )
    (net (code "116") (name "unconnected-(U4-PC1-Pad24)") (class "Default")
      (node (ref "U4") (pin "24") (pinfunction "PC1_24") (pintype "bidirectional"))
    )
    (net (code "117") (name "unconnected-(U4-PC4-Pad27)") (class "Default")
      (node (ref "U4") (pin "27") (pinfunction "PC4_27") (pintype "bidirectional"))
    )
    (net (code "118") (name "unconnected-(U4-PC5-Pad28)") (class "Default")
      (node (ref "U4") (pin "28") (pinfunction "PC5_28") (pintype "bidirectional"))
    )
    (net (code "119") (name "unconnected-(U4-PD0-Pad30)") (class "Default")
      (node (ref "U4") (pin "30") (pinfunction "PD0_30") (pintype "bidirectional"))
    )
    (net (code "120") (name "unconnected-(U4-PD1-Pad31)") (class "Default")
      (node (ref "U4") (pin "31") (pinfunction "PD1_31") (pintype "bidirectional"))
    )
    (net (code "121") (name "unconnected-(U4-PD3-Pad1)") (class "Default")
      (node (ref "U4") (pin "1") (pinfunction "PD3_1") (pintype "bidirectional"))
    )
    (net (code "122") (name "unconnected-(U4-PD5-Pad9)") (class "Default")
      (node (ref "U4") (pin "9") (pinfunction "PD5_9") (pintype "bidirectional"))
    )
    (net (code "123") (name "unconnected-(U4-PD6-Pad10)") (class "Default")
      (node (ref "U4") (pin "10") (pinfunction "PD6_10") (pintype "bidirectional"))
    )
  )
)
